# MultiNavFW_9250_RevA.net
KiCad netlist of a schematic drawn in EAGLE
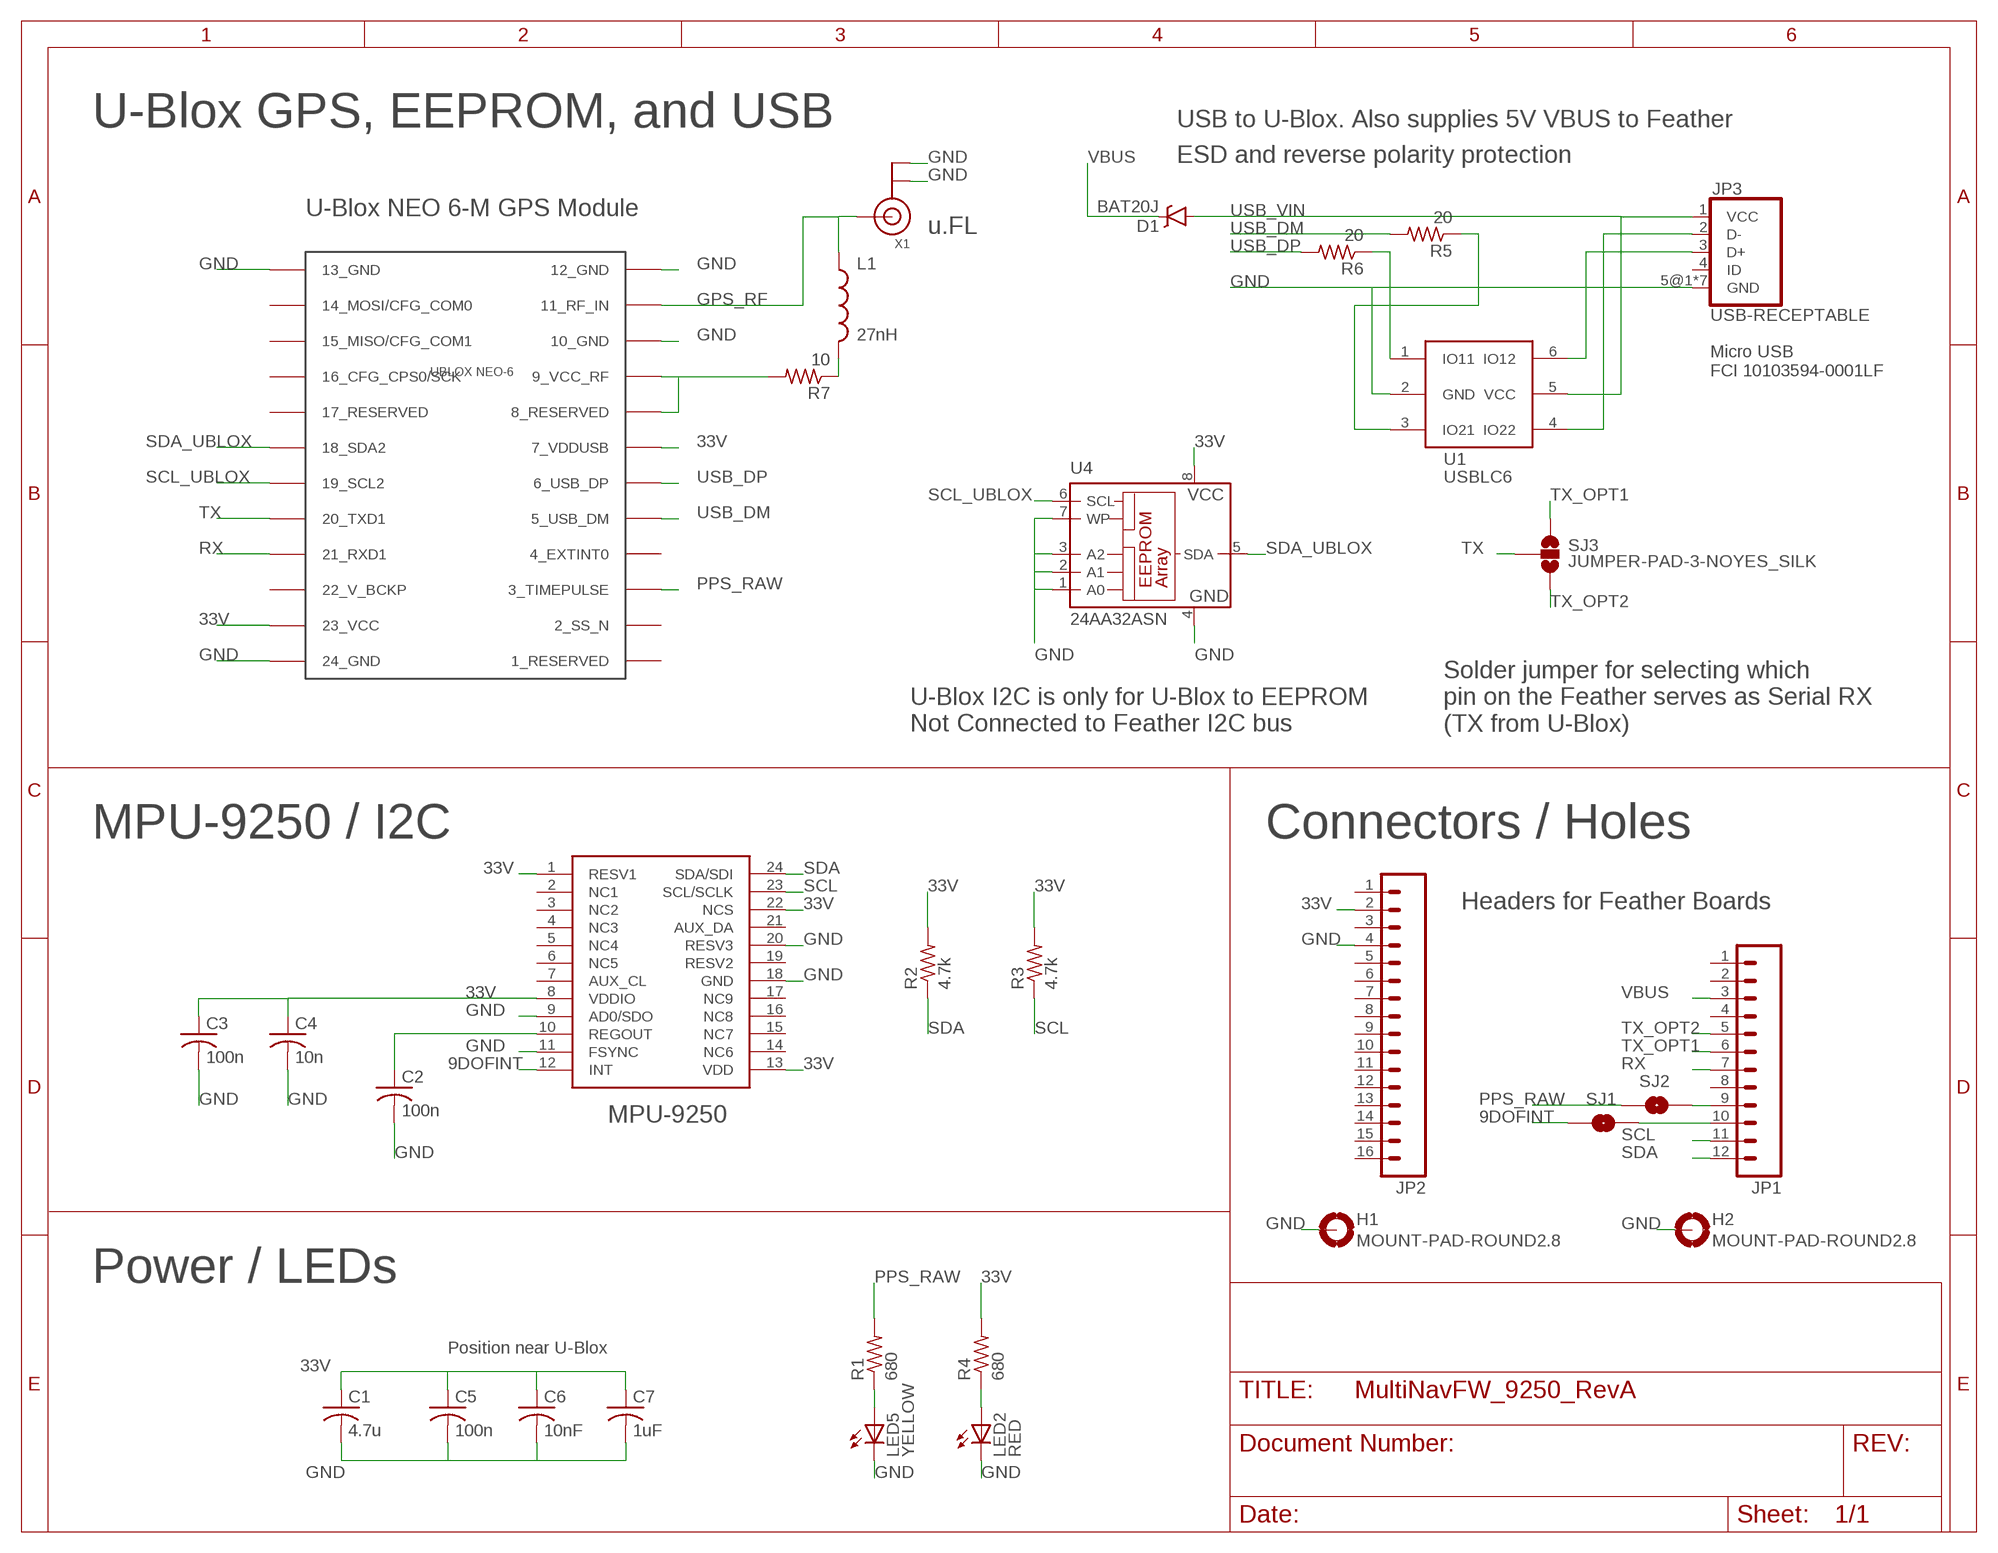
[diagram p0: schematic, sheet 1]

(export (version "E")
  (design (tool "Eeschema 10.0.6"))
  (components
    (comp (ref "C1")
      (value "4.7u")
      (footprint "eagle-import:C0603")
      (libsource (lib "eagle-import") (part "C-USC0603"))
    )
    (comp (ref "C2")
      (value "100n")
      (footprint "eagle-import:C0603")
      (libsource (lib "eagle-import") (part "C-USC0603"))
    )
    (comp (ref "C3")
      (value "100n")
      (footprint "eagle-import:C0603")
      (libsource (lib "eagle-import") (part "C-USC0603"))
    )
    (comp (ref "C4")
      (value "10n")
      (footprint "eagle-import:C0603")
      (libsource (lib "eagle-import") (part "C-USC0603"))
    )
    (comp (ref "C5")
      (value "100n")
      (footprint "eagle-import:C0603")
      (libsource (lib "eagle-import") (part "C-USC0603"))
    )
    (comp (ref "C6")
      (value "10nF")
      (footprint "eagle-import:C0603")
      (libsource (lib "eagle-import") (part "C-USC0603"))
    )
    (comp (ref "C7")
      (value "1uF")
      (footprint "eagle-import:C0603")
      (libsource (lib "eagle-import") (part "C-USC0603"))
    )
    (comp (ref "D1")
      (value "BAT20J")
      (footprint "eagle-import:SOD-323")
      (libsource (lib "eagle-import") (part "DIODE-SCHOTTKY-BAT20J"))
    )
    (comp (ref "H1")
      (value "MOUNT-PAD-ROUND2.8")
      (footprint "eagle-import:2,8-PAD")
      (libsource (lib "eagle-import") (part "MOUNT-PAD-ROUND2.8"))
    )
    (comp (ref "H2")
      (value "MOUNT-PAD-ROUND2.8")
      (footprint "eagle-import:2,8-PAD")
      (libsource (lib "eagle-import") (part "MOUNT-PAD-ROUND2.8"))
    )
    (comp (ref "JP1")
      (value "M12NO_SILK")
      (footprint "eagle-import:1X12_NO_SILK")
      (libsource (lib "eagle-import") (part "M12NO_SILK"))
    )
    (comp (ref "JP2")
      (value "M161X16_NO_SILK")
      (footprint "eagle-import:1X16_NO_SILK")
      (libsource (lib "eagle-import") (part "M161X16_NO_SILK"))
    )
    (comp (ref "JP3")
      (value "USB-RECEPTABLE")
      (footprint "eagle-import:FCI-10103594-0001LF")
      (libsource (lib "eagle-import") (part "USB-RECEPTABLE"))
    )
    (comp (ref "L1")
      (value "27nH")
      (footprint "eagle-import:C0402")
      (libsource (lib "eagle-import") (part "INDUCTOR0402"))
    )
    (comp (ref "LED2")
      (value "RED")
      (footprint "eagle-import:CHIPLED_0603")
      (libsource (lib "eagle-import") (part "LEDCHIPLED_0603"))
    )
    (comp (ref "LED5")
      (value "YELLOW")
      (footprint "eagle-import:CHIPLED_0603")
      (libsource (lib "eagle-import") (part "LEDCHIPLED_0603"))
    )
    (comp (ref "R1")
      (value "680")
      (footprint "eagle-import:R0603")
      (libsource (lib "eagle-import") (part "adafruit2_R-US_R0603"))
    )
    (comp (ref "R2")
      (value "4.7k")
      (footprint "eagle-import:R0603")
      (libsource (lib "eagle-import") (part "adafruit2_R-US_R0603"))
    )
    (comp (ref "R3")
      (value "4.7k")
      (footprint "eagle-import:R0603")
      (libsource (lib "eagle-import") (part "adafruit2_R-US_R0603"))
    )
    (comp (ref "R4")
      (value "680")
      (footprint "eagle-import:R0603")
      (libsource (lib "eagle-import") (part "adafruit2_R-US_R0603"))
    )
    (comp (ref "R5")
      (value "20")
      (footprint "eagle-import:R0603")
      (libsource (lib "eagle-import") (part "R-US_R0603"))
    )
    (comp (ref "R6")
      (value "20")
      (footprint "eagle-import:R0603")
      (libsource (lib "eagle-import") (part "R-US_R0603"))
    )
    (comp (ref "R7")
      (value "10")
      (footprint "eagle-import:R0603")
      (libsource (lib "eagle-import") (part "R-US_R0603"))
    )
    (comp (ref "SJ1")
      (value "SOLDERJUMPERNO")
      (footprint "eagle-import:SJ_2S-NO")
      (libsource (lib "eagle-import") (part "SOLDERJUMPERNO"))
    )
    (comp (ref "SJ2")
      (value "SOLDERJUMPERNO")
      (footprint "eagle-import:SJ_2S-NO")
      (libsource (lib "eagle-import") (part "SOLDERJUMPERNO"))
    )
    (comp (ref "SJ3")
      (value "JUMPER-PAD-3-NOYES_SILK")
      (footprint "eagle-import:PAD-JUMPER-3-NO_YES_SILK")
      (libsource (lib "eagle-import") (part "JUMPER-PAD-3-NOYES_SILK"))
    )
    (comp (ref "U1")
      (value "USBLC6-2")
      (footprint "eagle-import:SOT23-6")
      (libsource (lib "eagle-import") (part "USBLC6-2"))
    )
    (comp (ref "U2")
      (value "MPU-9250")
      (footprint "eagle-import:LEAD-QFN24")
      (libsource (lib "eagle-import") (part "MPU-9250"))
    )
    (comp (ref "U3")
      (value "UBLOX_NEO-6")
      (footprint "eagle-import:UBLOX_NEO-6P")
      (libsource (lib "eagle-import") (part "UBLOX_NEO-6"))
    )
    (comp (ref "U4")
      (value "24AA32ASN")
      (footprint "eagle-import:SO-08")
      (fields (field (name "MF") "MICROCHIP") (field (name "MPN") "24AA32A-I/SN"))
      (libsource (lib "eagle-import") (part "24SNAA32A"))
    )
    (comp (ref "X1")
      (value "ANTENNA_U.FL")
      (footprint "eagle-import:U.FL")
      (libsource (lib "eagle-import") (part "ANTENNA_U.FL"))
    )
  )
  (nets
    (net (code "1") (name "/9DOFINT") (class "Default")
      (node (ref "SJ1") (pin "1") (pinfunction "1_1") (pintype "passive"))
      (node (ref "U2") (pin "12") (pinfunction "INT_12") (pintype "bidirectional"))
    )
    (net (code "2") (name "/33V") (class "Default")
      (node (ref "C1") (pin "1") (pinfunction "1_1") (pintype "passive"))
      (node (ref "C3") (pin "1") (pinfunction "1_1") (pintype "passive"))
      (node (ref "C4") (pin "1") (pinfunction "1_1") (pintype "passive"))
      (node (ref "C5") (pin "1") (pinfunction "1_1") (pintype "passive"))
      (node (ref "C6") (pin "1") (pinfunction "1_1") (pintype "passive"))
      (node (ref "C7") (pin "1") (pinfunction "1_1") (pintype "passive"))
      (node (ref "JP2") (pin "2") (pinfunction "2_2") (pintype "passive"))
      (node (ref "R2") (pin "2") (pinfunction "2_2") (pintype "passive"))
      (node (ref "R3") (pin "2") (pinfunction "2_2") (pintype "passive"))
      (node (ref "R4") (pin "2") (pinfunction "2_2") (pintype "passive"))
      (node (ref "U2") (pin "1") (pinfunction "RESV1_1") (pintype "bidirectional"))
      (node (ref "U2") (pin "13") (pinfunction "VDD_13") (pintype "bidirectional"))
      (node (ref "U2") (pin "22") (pinfunction "NCS_22") (pintype "bidirectional"))
      (node (ref "U2") (pin "8") (pinfunction "VDDIO_8") (pintype "bidirectional"))
      (node (ref "U3") (pin "23_VCC") (pinfunction "23_VCC_23_VCC") (pintype "bidirectional"))
      (node (ref "U3") (pin "7_VDDUSB") (pinfunction "7_VDDUSB_7_VDDUSB") (pintype "bidirectional"))
      (node (ref "U4") (pin "8") (pinfunction "VCC_8") (pintype "power_in"))
    )
    (net (code "3") (name "/GND") (class "Default")
      (node (ref "C1") (pin "2") (pinfunction "2_2") (pintype "passive"))
      (node (ref "C2") (pin "2") (pinfunction "2_2") (pintype "passive"))
      (node (ref "C3") (pin "2") (pinfunction "2_2") (pintype "passive"))
      (node (ref "C4") (pin "2") (pinfunction "2_2") (pintype "passive"))
      (node (ref "C5") (pin "2") (pinfunction "2_2") (pintype "passive"))
      (node (ref "C6") (pin "2") (pinfunction "2_2") (pintype "passive"))
      (node (ref "C7") (pin "2") (pinfunction "2_2") (pintype "passive"))
      (node (ref "H1") (pin "B2,8") (pinfunction "MOUNT_B2,8") (pintype "passive"))
      (node (ref "H2") (pin "B2,8") (pinfunction "MOUNT_B2,8") (pintype "passive"))
      (node (ref "JP2") (pin "4") (pinfunction "4_4") (pintype "passive"))
      (node (ref "JP3") (pin "5@1") (pinfunction "GND_5@1") (pintype "bidirectional"))
      (node (ref "JP3") (pin "5@2") (pinfunction "GND_5@2") (pintype "bidirectional"))
      (node (ref "JP3") (pin "5@3") (pinfunction "GND_5@3") (pintype "bidirectional"))
      (node (ref "JP3") (pin "5@4") (pinfunction "GND_5@4") (pintype "bidirectional"))
      (node (ref "JP3") (pin "5@5") (pinfunction "GND_5@5") (pintype "bidirectional"))
      (node (ref "JP3") (pin "5@6") (pinfunction "GND_5@6") (pintype "bidirectional"))
      (node (ref "JP3") (pin "5@7") (pinfunction "GND_5@7") (pintype "bidirectional"))
      (node (ref "LED2") (pin "C") (pinfunction "C_C") (pintype "passive"))
      (node (ref "LED5") (pin "C") (pinfunction "C_C") (pintype "passive"))
      (node (ref "U1") (pin "2") (pinfunction "GND_2") (pintype "bidirectional"))
      (node (ref "U2") (pin "11") (pinfunction "FSYNC_11") (pintype "bidirectional"))
      (node (ref "U2") (pin "18") (pinfunction "GND_18") (pintype "bidirectional"))
      (node (ref "U2") (pin "20") (pinfunction "RESV3_20") (pintype "bidirectional"))
      (node (ref "U2") (pin "9") (pinfunction "AD0/SDO_9") (pintype "bidirectional"))
      (node (ref "U3") (pin "10_GND") (pinfunction "10_GND_10_GND") (pintype "bidirectional"))
      (node (ref "U3") (pin "12_GND") (pinfunction "12_GND_12_GND") (pintype "bidirectional"))
      (node (ref "U3") (pin "13_GND") (pinfunction "13_GND_13_GND") (pintype "bidirectional"))
      (node (ref "U3") (pin "24_GND") (pinfunction "24_GND_24_GND") (pintype "bidirectional"))
      (node (ref "U4") (pin "1") (pinfunction "A0_1") (pintype "input"))
      (node (ref "U4") (pin "2") (pinfunction "A1_2") (pintype "input"))
      (node (ref "U4") (pin "3") (pinfunction "A2_3") (pintype "input"))
      (node (ref "U4") (pin "4") (pinfunction "GND_4") (pintype "power_in"))
      (node (ref "U4") (pin "7") (pinfunction "WP_7") (pintype "input"))
      (node (ref "X1") (pin "1") (pinfunction "GND_1") (pintype "passive"))
      (node (ref "X1") (pin "2") (pinfunction "GND_2") (pintype "passive"))
    )
    (net (code "4") (name "/GPS_RF") (class "Default")
      (node (ref "L1") (pin "1") (pinfunction "1_1") (pintype "passive"))
      (node (ref "U3") (pin "11_RF_IN") (pinfunction "11_RF_IN_11_RF_IN") (pintype "bidirectional"))
      (node (ref "X1") (pin "3") (pinfunction "SIGNAL_3") (pintype "passive"))
    )
    (net (code "5") (name "/PPS_RAW") (class "Default")
      (node (ref "R1") (pin "2") (pinfunction "2_2") (pintype "passive"))
      (node (ref "SJ2") (pin "1") (pinfunction "1_1") (pintype "passive"))
      (node (ref "U3") (pin "3_TIMEPULSE") (pinfunction "3_TIMEPULSE_3_TIMEPULSE") (pintype "bidirectional"))
    )
    (net (code "6") (name "/RX") (class "Default")
      (node (ref "JP1") (pin "7") (pinfunction "7_7") (pintype "passive"))
      (node (ref "U3") (pin "21_RXD1") (pinfunction "21_RXD1_21_RXD1") (pintype "bidirectional"))
    )
    (net (code "7") (name "/SCL") (class "Default")
      (node (ref "JP1") (pin "11") (pinfunction "11_11") (pintype "passive"))
      (node (ref "R3") (pin "1") (pinfunction "1_1") (pintype "passive"))
      (node (ref "U2") (pin "23") (pinfunction "SCL/SCLK_23") (pintype "bidirectional"))
    )
    (net (code "8") (name "/SCL_UBLOX") (class "Default")
      (node (ref "U3") (pin "19_SCL2") (pinfunction "19_SCL2_19_SCL2") (pintype "bidirectional"))
      (node (ref "U4") (pin "6") (pinfunction "SCL_6") (pintype "input"))
    )
    (net (code "9") (name "/SDA") (class "Default")
      (node (ref "JP1") (pin "12") (pinfunction "12_12") (pintype "passive"))
      (node (ref "R2") (pin "1") (pinfunction "1_1") (pintype "passive"))
      (node (ref "U2") (pin "24") (pinfunction "SDA/SDI_24") (pintype "bidirectional"))
    )
    (net (code "10") (name "/SDA_UBLOX") (class "Default")
      (node (ref "U3") (pin "18_SDA2") (pinfunction "18_SDA2_18_SDA2") (pintype "bidirectional"))
      (node (ref "U4") (pin "5") (pinfunction "SDA_5") (pintype "bidirectional"))
    )
    (net (code "11") (name "/TX") (class "Default")
      (node (ref "SJ3") (pin "2") (pinfunction "2_2") (pintype "passive"))
      (node (ref "U3") (pin "20_TXD1") (pinfunction "20_TXD1_20_TXD1") (pintype "bidirectional"))
    )
    (net (code "12") (name "/TX_OPT1") (class "Default")
      (node (ref "JP1") (pin "6") (pinfunction "6_6") (pintype "passive"))
      (node (ref "SJ3") (pin "1") (pinfunction "1_1") (pintype "passive"))
    )
    (net (code "13") (name "/TX_OPT2") (class "Default")
      (node (ref "JP1") (pin "5") (pinfunction "5_5") (pintype "passive"))
      (node (ref "SJ3") (pin "3") (pinfunction "3_3") (pintype "passive"))
    )
    (net (code "14") (name "/USB_DM") (class "Default")
      (node (ref "R5") (pin "2") (pinfunction "2_2") (pintype "passive"))
      (node (ref "U3") (pin "5_USB_DM") (pinfunction "5_USB_DM_5_USB_DM") (pintype "bidirectional"))
    )
    (net (code "15") (name "/USB_DP") (class "Default")
      (node (ref "R6") (pin "2") (pinfunction "2_2") (pintype "passive"))
      (node (ref "U3") (pin "6_USB_DP") (pinfunction "6_USB_DP_6_USB_DP") (pintype "bidirectional"))
    )
    (net (code "16") (name "/USB_VIN") (class "Default")
      (node (ref "D1") (pin "A") (pinfunction "A_A") (pintype "passive"))
      (node (ref "JP3") (pin "1") (pinfunction "VCC_1") (pintype "bidirectional"))
      (node (ref "U1") (pin "5") (pinfunction "VCC_5") (pintype "bidirectional"))
    )
    (net (code "17") (name "/VBUS") (class "Default")
      (node (ref "D1") (pin "C") (pinfunction "C_C") (pintype "passive"))
      (node (ref "JP1") (pin "3") (pinfunction "3_3") (pintype "passive"))
    )
    (net (code "18") (name "Net-(JP1-Pad9)") (class "Default")
      (node (ref "JP1") (pin "9") (pinfunction "9_9") (pintype "passive"))
      (node (ref "SJ2") (pin "2") (pinfunction "2_2") (pintype "passive"))
    )
    (net (code "19") (name "Net-(JP1-Pad10)") (class "Default")
      (node (ref "JP1") (pin "10") (pinfunction "10_10") (pintype "passive"))
      (node (ref "SJ1") (pin "2") (pinfunction "2_2") (pintype "passive"))
    )
    (net (code "20") (name "Net-(JP3-D+)") (class "Default")
      (node (ref "JP3") (pin "3") (pinfunction "D+_3") (pintype "bidirectional"))
      (node (ref "U1") (pin "6") (pinfunction "IO12_6") (pintype "bidirectional"))
    )
    (net (code "21") (name "Net-(JP3-D-)") (class "Default")
      (node (ref "JP3") (pin "2") (pinfunction "D-_2") (pintype "bidirectional"))
      (node (ref "U1") (pin "4") (pinfunction "IO22_4") (pintype "bidirectional"))
    )
    (net (code "22") (name "Net-(L1-Pad2)") (class "Default")
      (node (ref "L1") (pin "2") (pinfunction "2_2") (pintype "passive"))
      (node (ref "R7") (pin "1") (pinfunction "1_1") (pintype "passive"))
    )
    (net (code "23") (name "Net-(LED2-PadA)") (class "Default")
      (node (ref "LED2") (pin "A") (pinfunction "A_A") (pintype "passive"))
      (node (ref "R4") (pin "1") (pinfunction "1_1") (pintype "passive"))
    )
    (net (code "24") (name "Net-(LED5-PadA)") (class "Default")
      (node (ref "LED5") (pin "A") (pinfunction "A_A") (pintype "passive"))
      (node (ref "R1") (pin "1") (pinfunction "1_1") (pintype "passive"))
    )
    (net (code "25") (name "Net-(R7-Pad2)") (class "Default")
      (node (ref "R7") (pin "2") (pinfunction "2_2") (pintype "passive"))
      (node (ref "U3") (pin "8_RESERVED") (pinfunction "8_RESERVED_8_RESERVED") (pintype "bidirectional"))
      (node (ref "U3") (pin "9_VCC_RF") (pinfunction "9_VCC_RF_9_VCC_RF") (pintype "bidirectional"))
    )
    (net (code "26") (name "Net-(U1-IO11)") (class "Default")
      (node (ref "R6") (pin "1") (pinfunction "1_1") (pintype "passive"))
      (node (ref "U1") (pin "1") (pinfunction "IO11_1") (pintype "bidirectional"))
    )
    (net (code "27") (name "Net-(U1-IO21)") (class "Default")
      (node (ref "R5") (pin "1") (pinfunction "1_1") (pintype "passive"))
      (node (ref "U1") (pin "3") (pinfunction "IO21_3") (pintype "bidirectional"))
    )
    (net (code "28") (name "Net-(U2-REGOUT)") (class "Default")
      (node (ref "C2") (pin "1") (pinfunction "1_1") (pintype "passive"))
      (node (ref "U2") (pin "10") (pinfunction "REGOUT_10") (pintype "bidirectional"))
    )
    (net (code "29") (name "unconnected-(JP1-Pad1)") (class "Default")
      (node (ref "JP1") (pin "1") (pinfunction "1_1") (pintype "passive"))
    )
    (net (code "30") (name "unconnected-(JP1-Pad2)") (class "Default")
      (node (ref "JP1") (pin "2") (pinfunction "2_2") (pintype "passive"))
    )
    (net (code "31") (name "unconnected-(JP1-Pad4)") (class "Default")
      (node (ref "JP1") (pin "4") (pinfunction "4_4") (pintype "passive"))
    )
    (net (code "32") (name "unconnected-(JP1-Pad8)") (class "Default")
      (node (ref "JP1") (pin "8") (pinfunction "8_8") (pintype "passive"))
    )
    (net (code "33") (name "unconnected-(JP2-Pad1)") (class "Default")
      (node (ref "JP2") (pin "1") (pinfunction "1_1") (pintype "passive"))
    )
    (net (code "34") (name "unconnected-(JP2-Pad3)") (class "Default")
      (node (ref "JP2") (pin "3") (pinfunction "3_3") (pintype "passive"))
    )
    (net (code "35") (name "unconnected-(JP2-Pad5)") (class "Default")
      (node (ref "JP2") (pin "5") (pinfunction "5_5") (pintype "passive"))
    )
    (net (code "36") (name "unconnected-(JP2-Pad6)") (class "Default")
      (node (ref "JP2") (pin "6") (pinfunction "6_6") (pintype "passive"))
    )
    (net (code "37") (name "unconnected-(JP2-Pad7)") (class "Default")
      (node (ref "JP2") (pin "7") (pinfunction "7_7") (pintype "passive"))
    )
    (net (code "38") (name "unconnected-(JP2-Pad8)") (class "Default")
      (node (ref "JP2") (pin "8") (pinfunction "8_8") (pintype "passive"))
    )
    (net (code "39") (name "unconnected-(JP2-Pad9)") (class "Default")
      (node (ref "JP2") (pin "9") (pinfunction "9_9") (pintype "passive"))
    )
    (net (code "40") (name "unconnected-(JP2-Pad10)") (class "Default")
      (node (ref "JP2") (pin "10") (pinfunction "10_10") (pintype "passive"))
    )
    (net (code "41") (name "unconnected-(JP2-Pad11)") (class "Default")
      (node (ref "JP2") (pin "11") (pinfunction "11_11") (pintype "passive"))
    )
    (net (code "42") (name "unconnected-(JP2-Pad12)") (class "Default")
      (node (ref "JP2") (pin "12") (pinfunction "12_12") (pintype "passive"))
    )
    (net (code "43") (name "unconnected-(JP2-Pad13)") (class "Default")
      (node (ref "JP2") (pin "13") (pinfunction "13_13") (pintype "passive"))
    )
    (net (code "44") (name "unconnected-(JP2-Pad14)") (class "Default")
      (node (ref "JP2") (pin "14") (pinfunction "14_14") (pintype "passive"))
    )
    (net (code "45") (name "unconnected-(JP2-Pad15)") (class "Default")
      (node (ref "JP2") (pin "15") (pinfunction "15_15") (pintype "passive"))
    )
    (net (code "46") (name "unconnected-(JP2-Pad16)") (class "Default")
      (node (ref "JP2") (pin "16") (pinfunction "16_16") (pintype "passive"))
    )
    (net (code "47") (name "unconnected-(JP3-ID-Pad4)") (class "Default")
      (node (ref "JP3") (pin "4") (pinfunction "ID_4") (pintype "bidirectional"))
    )
    (net (code "48") (name "unconnected-(U2-AUX_CL-Pad7)") (class "Default")
      (node (ref "U2") (pin "7") (pinfunction "AUX_CL_7") (pintype "bidirectional"))
    )
    (net (code "49") (name "unconnected-(U2-AUX_DA-Pad21)") (class "Default")
      (node (ref "U2") (pin "21") (pinfunction "AUX_DA_21") (pintype "bidirectional"))
    )
    (net (code "50") (name "unconnected-(U2-NC1-Pad2)") (class "Default")
      (node (ref "U2") (pin "2") (pinfunction "NC1_2") (pintype "bidirectional"))
    )
    (net (code "51") (name "unconnected-(U2-NC2-Pad3)") (class "Default")
      (node (ref "U2") (pin "3") (pinfunction "NC2_3") (pintype "bidirectional"))
    )
    (net (code "52") (name "unconnected-(U2-NC3-Pad4)") (class "Default")
      (node (ref "U2") (pin "4") (pinfunction "NC3_4") (pintype "bidirectional"))
    )
    (net (code "53") (name "unconnected-(U2-NC4-Pad5)") (class "Default")
      (node (ref "U2") (pin "5") (pinfunction "NC4_5") (pintype "bidirectional"))
    )
    (net (code "54") (name "unconnected-(U2-NC5-Pad6)") (class "Default")
      (node (ref "U2") (pin "6") (pinfunction "NC5_6") (pintype "bidirectional"))
    )
    (net (code "55") (name "unconnected-(U2-NC6-Pad14)") (class "Default")
      (node (ref "U2") (pin "14") (pinfunction "NC6_14") (pintype "bidirectional"))
    )
    (net (code "56") (name "unconnected-(U2-NC7-Pad15)") (class "Default")
      (node (ref "U2") (pin "15") (pinfunction "NC7_15") (pintype "bidirectional"))
    )
    (net (code "57") (name "unconnected-(U2-NC8-Pad16)") (class "Default")
      (node (ref "U2") (pin "16") (pinfunction "NC8_16") (pintype "bidirectional"))
    )
    (net (code "58") (name "unconnected-(U2-NC9-Pad17)") (class "Default")
      (node (ref "U2") (pin "17") (pinfunction "NC9_17") (pintype "bidirectional"))
    )
    (net (code "59") (name "unconnected-(U2-RESV2-Pad19)") (class "Default")
      (node (ref "U2") (pin "19") (pinfunction "RESV2_19") (pintype "bidirectional"))
    )
    (net (code "60") (name "unconnected-(U3-Pad1_RESERVED)") (class "Default")
      (node (ref "U3") (pin "1_RESERVED") (pinfunction "1_RESERVED_1_RESERVED") (pintype "bidirectional"))
    )
    (net (code "61") (name "unconnected-(U3-Pad2_SS_N)") (class "Default")
      (node (ref "U3") (pin "2_SS_N") (pinfunction "2_SS_N_2_SS_N") (pintype "bidirectional"))
    )
    (net (code "62") (name "unconnected-(U3-Pad4_EXTINT0)") (class "Default")
      (node (ref "U3") (pin "4_EXTINT0") (pinfunction "4_EXTINT0_4_EXTINT0") (pintype "bidirectional"))
    )
    (net (code "63") (name "unconnected-(U3-Pad14_MOSI{slash}CFG_COM0)") (class "Default")
      (node (ref "U3") (pin "14_MOSI/CFG_COM0") (pinfunction "14_MOSI/CFG_COM0_14_MOSI/CFG_COM0") (pintype "bidirectional"))
    )
    (net (code "64") (name "unconnected-(U3-Pad15_MISO{slash}CFG_COM1)") (class "Default")
      (node (ref "U3") (pin "15_MISO/CFG_COM1") (pinfunction "15_MISO/CFG_COM1_15_MISO/CFG_COM1") (pintype "bidirectional"))
    )
    (net (code "65") (name "unconnected-(U3-Pad16_CFG_CPS0{slash}SCK)") (class "Default")
      (node (ref "U3") (pin "16_CFG_CPS0/SCK") (pinfunction "16_CFG_CPS0/SCK_16_CFG_CPS0/SCK") (pintype "bidirectional"))
    )
    (net (code "66") (name "unconnected-(U3-Pad17_RESERVED)") (class "Default")
      (node (ref "U3") (pin "17_RESERVED") (pinfunction "17_RESERVED_17_RESERVED") (pintype "bidirectional"))
    )
    (net (code "67") (name "unconnected-(U3-Pad22_V_BCKP)") (class "Default")
      (node (ref "U3") (pin "22_V_BCKP") (pinfunction "22_V_BCKP_22_V_BCKP") (pintype "bidirectional"))
    )
  )
)
